# MCU.net
KiCad netlist of a schematic drawn in Altium Designer
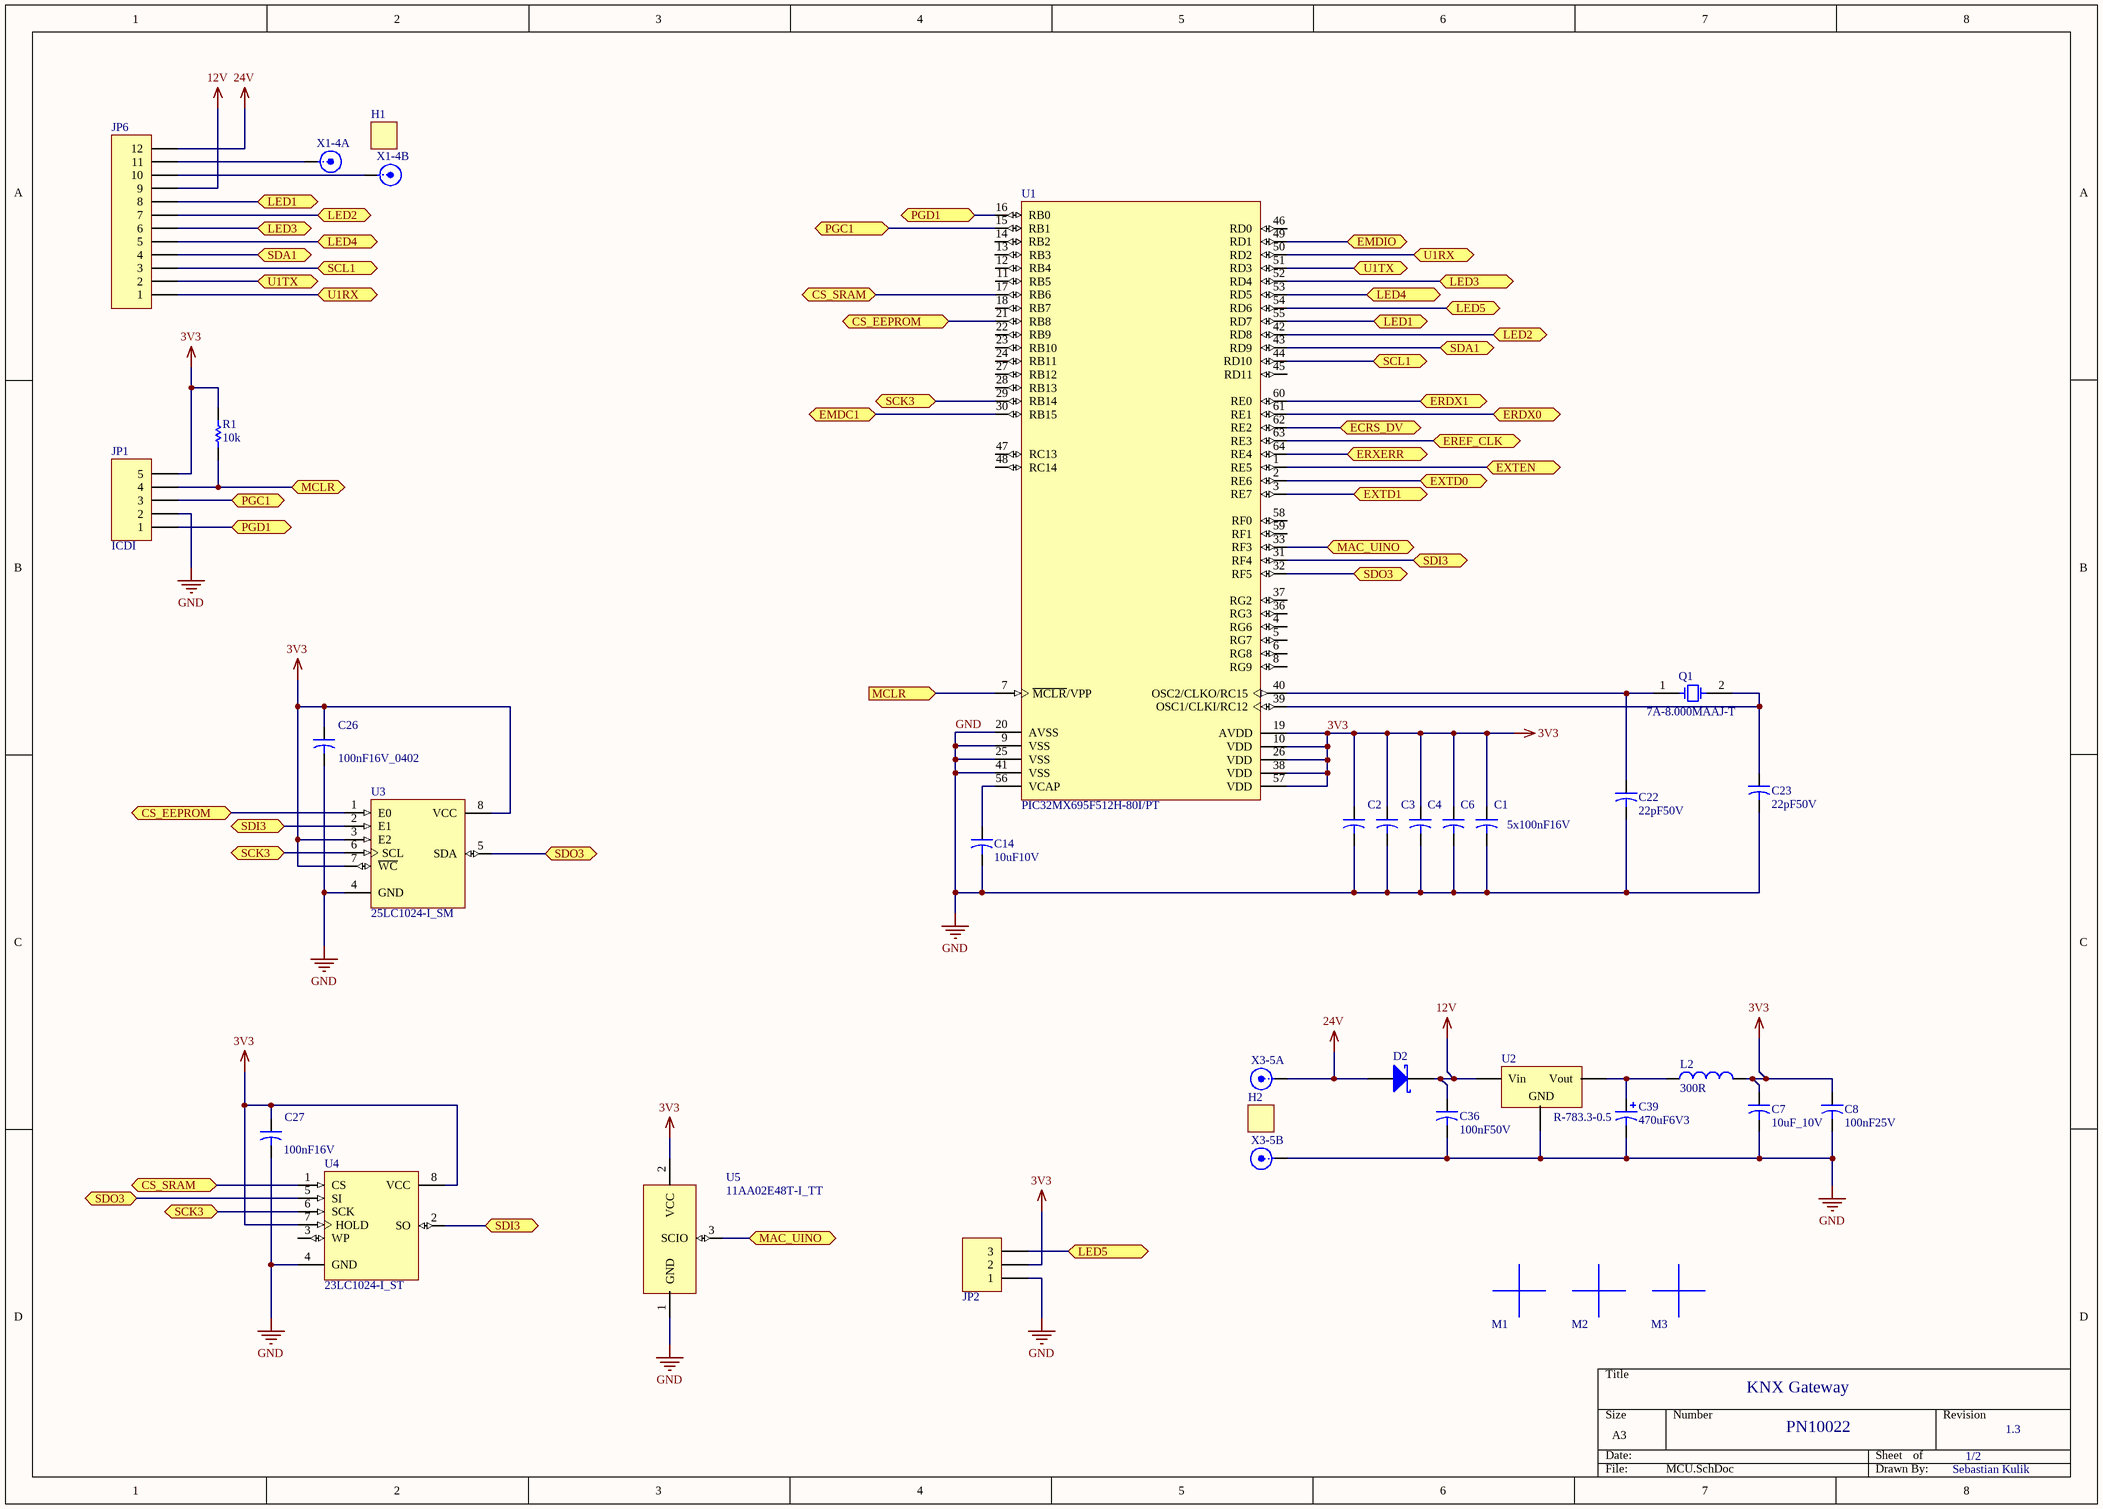
[diagram p0: MCU.SchDoc]

(export (version "E")
  (design (tool "Eeschema 10.0.6"))
  (components
    (comp (ref "C1")
      (value "100nF16V_0402")
      (footprint "C0402")
      (description "Capacitor")
      (fields (field (name "MANUFACTURER") "TDK") (field (name "PUBLISHER") "Sebastian Kulik"))
      (libsource (lib "Capacitors") (part "100nF16V_0402"))
    )
    (comp (ref "C2")
      (value "100nF16V_0402")
      (footprint "C0402")
      (description "Capacitor")
      (fields (field (name "MANUFACTURER") "TDK") (field (name "PUBLISHER") "Sebastian Kulik"))
      (libsource (lib "Capacitors") (part "100nF16V_0402"))
    )
    (comp (ref "C3")
      (value "100nF16V_0402")
      (footprint "C0402")
      (description "Capacitor")
      (fields (field (name "MANUFACTURER") "TDK") (field (name "PUBLISHER") "Sebastian Kulik"))
      (libsource (lib "Capacitors") (part "100nF16V_0402"))
    )
    (comp (ref "C4")
      (value "100nF16V_0402")
      (footprint "C0402")
      (description "Capacitor")
      (fields (field (name "MANUFACTURER") "TDK") (field (name "PUBLISHER") "Sebastian Kulik"))
      (libsource (lib "Capacitors") (part "100nF16V_0402"))
    )
    (comp (ref "C6")
      (value "100nF16V_0402")
      (footprint "C0402")
      (description "Capacitor")
      (fields (field (name "MANUFACTURER") "TDK") (field (name "PUBLISHER") "Sebastian Kulik"))
      (libsource (lib "Capacitors") (part "100nF16V_0402"))
    )
    (comp (ref "C7")
      (value "10uF_10V")
      (footprint "C0603")
      (description "AVX ,  X5R, 20%, 10V")
      (fields
        (field (name "MANUFACTURER") "AVX")
        (field (name "Comment") "10uF10V_0603")
        (field (name "PUBLISHER") "Sebastian Kulik")
      )
      (libsource (lib "Capacitors") (part "10uF10V_0603"))
    )
    (comp (ref "C8")
      (value "100nF25V")
      (footprint "C0402")
      (description "AVX, X5R, 10%, 25V")
      (fields
        (field (name "MANUFACTURER") "AVX")
        (field (name "Comment") "100nF25V_0402")
        (field (name "PUBLISHER") "Sebastian Kulik")
      )
      (libsource (lib "Capacitors") (part "100nF25V_0402"))
    )
    (comp (ref "C14")
      (value "10uF10V")
      (footprint "C0603")
      (description "Capacitor")
      (fields
        (field (name "MANUFACTURER") "AVX")
        (field (name "Comment") "10uF10V_0603")
        (field (name "PUBLISHER") "Sebastian Kulik")
      )
      (libsource (lib "Capacitors") (part "10uF10V_0603"))
    )
    (comp (ref "C22")
      (value "22pF50V")
      (footprint "C0402")
      (description "AVX, 50V")
      (fields
        (field (name "MANUFACTURER") "AVX")
        (field (name "Comment") "22pF50V_0402-AVX")
        (field (name "PUBLISHER") "Sebastian Kulik")
      )
      (libsource (lib "Capacitors") (part "22pF50V_0402-AVX"))
    )
    (comp (ref "C23")
      (value "22pF50V")
      (footprint "C0402")
      (description "AVX, 50V")
      (fields
        (field (name "MANUFACTURER") "AVX")
        (field (name "Comment") "22pF50V_0402-AVX")
        (field (name "PUBLISHER") "Sebastian Kulik")
      )
      (libsource (lib "Capacitors") (part "22pF50V_0402-AVX"))
    )
    (comp (ref "C26")
      (value "100nF16V_0402")
      (footprint "C0402")
      (description "Capacitor")
      (fields (field (name "MANUFACTURER") "TDK") (field (name "PUBLISHER") "Sebastian Kulik"))
      (libsource (lib "Capacitors") (part "100nF16V_0402"))
    )
    (comp (ref "C27")
      (value "100nF16V")
      (footprint "C0402")
      (description "Capacitor")
      (fields
        (field (name "MANUFACTURER") "TDK")
        (field (name "Comment") "100nF16V_0402")
        (field (name "PUBLISHER") "Sebastian Kulik")
      )
      (libsource (lib "Capacitors") (part "100nF16V_0402"))
    )
    (comp (ref "C36")
      (value "100nF50V")
      (footprint "C0402")
      (description "C series, X5R, 10%, 50V")
      (fields
        (field (name "MANUFACTURER") "TDK")
        (field (name "Comment") "100n50V_0402")
        (field (name "PUBLISHER") "Sebastian Kulik")
      )
      (libsource (lib "Capacitors") (part "100n50V_0402"))
    )
    (comp (ref "C39")
      (value "470uF6V3")
      (footprint "Panasonic_TPE-D4")
      (description "TPE-4D series, tantal, 10%, 6.3V")
      (fields
        (field (name "MANUFACTURER") "Panasonic")
        (field (name "Comment") "470uF_6V3_TPE-4D")
        (field (name "PUBLISHER") "Sebastian Kulik")
      )
      (libsource (lib "Capacitors") (part "470uF_6V3_TPE-4D"))
    )
    (comp (ref "D2")
      (value "RB160M-30TR")
      (footprint "SOD123")
      (description "Diode Schottky,2A,40V")
      (fields (field (name "MANUFACTURER") "Rohm") (field (name "PUBLISHER") "Sebastian Kulik"))
      (libsource (lib "Discrete") (part "RB160M-30TR"))
    )
    (comp (ref "H1")
      (value "Wago-243-211")
      (footprint "WAGO-243-211")
      (fields (field (name "MANUFACTURER") "Wago") (field (name "PUBLISHER") "Sebastian Kulik"))
      (libsource (lib "Connectors") (part "Wago-243-211"))
    )
    (comp (ref "H2")
      (value "Wago-243-211")
      (footprint "WAGO-243-211")
      (fields (field (name "MANUFACTURER") "Wago") (field (name "PUBLISHER") "Sebastian Kulik"))
      (libsource (lib "Connectors") (part "Wago-243-211"))
    )
    (comp (ref "JP1")
      (value "ICDI")
      (footprint "HDR1X5-1.27")
      (description "Header, 5-Pin")
      (fields (field (name "PUBLISHER") "Sebastian Kulik"))
      (libsource (lib "Connectors") (part "ICDI"))
    )
    (comp (ref "JP2")
      (value "Header-3")
      (footprint "HDR1X3")
      (description "Header-3-Pin")
      (fields (field (name "PUBLISHER") "Sebastian Kulik"))
      (libsource (lib "Connectors") (part "Header-3"))
    )
    (comp (ref "JP6")
      (value "Plug_12_2.54")
      (footprint "HDR1X12_2.54")
      (description "Plug, 11-Pin")
      (fields (field (name "MANUFACTURER") "WE") (field (name "PUBLISHER") "Sebastian Kulik"))
      (libsource (lib "Connectors") (part "Plug_12_2.54"))
    )
    (comp (ref "L2")
      (value "300R")
      (footprint "L0603")
      (description "WE, Ferrit, 300Rx2A")
      (fields
        (field (name "MANUFACTURER") "WE")
        (field (name "Comment") "300R2A_0603")
        (field (name "PUBLISHER") "Sebastian Kulik")
      )
      (libsource (lib "Passives") (part "300R2A_0603"))
    )
    (comp (ref "M1") (value "Paste-Mark") (footprint "Mark-3mm") (libsource (lib "Symbols") (part "Mark")))
    (comp (ref "M2") (value "Paste-Mark") (footprint "Mark-3mm") (libsource (lib "Symbols") (part "Mark")))
    (comp (ref "M3") (value "Paste-Mark") (footprint "Mark-3mm") (libsource (lib "Symbols") (part "Mark")))
    (comp (ref "Q1")
      (value "7A-8.000MAAJ-T")
      (footprint "TXC_7A")
      (description "Crystal, 7A-8.000MAAJ-T")
      (fields (field (name "MANUFACTURER") "TXC") (field (name "PUBLISHER") "Sebastian Kulik"))
      (libsource (lib "Passives") (part "Crystal_8MHz"))
    )
    (comp (ref "R1")
      (value "10k")
      (footprint "R0402")
      (description "Vishay CRCW series, 125mW, 1%")
      (fields
        (field (name "MANUFACTURER") "Vishay")
        (field (name "Comment") "10k_0402")
        (field (name "PUBLISHER") "Sebastian Kulik")
      )
      (libsource (lib "Resistors") (part "10k_0402"))
    )
    (comp (ref "U1")
      (value "PIC32MX695F512H-80I/PT")
      (footprint "TQFP-64_N1")
      (fields (field (name "MANUFACTURER") "Microchip") (field (name "PUBLISHER") "Sebastian Kulik"))
      (libsource (lib "ICs") (part "PIC32MX695F512H-80I/PT"))
    )
    (comp (ref "U2")
      (value "R-783.3-0.5")
      (footprint "R-783_3-0_5")
      (description "Voltage Regulator")
      (fields (field (name "MANUFACTURER") "Recom") (field (name "PUBLISHER") "Sebastian Kulik"))
      (libsource (lib "ICs") (part "Recom-R-783_3-0_5"))
    )
    (comp (ref "U3")
      (value "25LC1024-I_SM")
      (footprint "SOP8_N")
      (description "1024 Kbit Serial SPI Bus EEPROM")
      (fields (field (name "MANUFACTURER") "Microchip") (field (name "PUBLISHER") "Sebastian Kulik"))
      (libsource (lib "ICs") (part "25LC1024-I_SM"))
    )
    (comp (ref "U4")
      (value "23LC1024-I_ST")
      (footprint "TSSOP8")
      (description "1 Mbit Serial  EEPROM")
      (fields (field (name "MANUFACTURER") "Microchip") (field (name "PUBLISHER") "Sebastian Kulik"))
      (libsource (lib "ICs") (part "23LC1024-I_ST"))
    )
    (comp (ref "U5")
      (value "11AA02E48T-I_TT")
      (footprint "SOT23_M")
      (description "2 kbit Serial  EEPROM")
      (fields (field (name "MANUFACTURER") "Microchip") (field (name "PUBLISHER") "Sebastian Kulik"))
      (libsource (lib "ICs") (part "11AA02E48T-I_TT"))
    )
    (comp (ref "X1-4")
      (value "Wago-243-131")
      (footprint "WAGO-243-131")
      (fields (field (name "MANUFACTURER") "Wago") (field (name "PUBLISHER") "Sebastian Kulik"))
      (libsource (lib "") (part "Wago-243-131_2"))
    )
    (comp (ref "X3-5")
      (value "Wago-243-131")
      (footprint "WAGO-243-131")
      (fields (field (name "MANUFACTURER") "Wago") (field (name "PUBLISHER") "Sebastian Kulik"))
      (libsource (lib "") (part "Wago-243-131_1"))
    )
  )
  (nets
    (net (code "1") (name "/CS_EEPROM") (class "Default")
      (node (ref "U1") (pin "21") (pinfunction "RB8_21") (pintype "bidirectional"))
      (node (ref "U3") (pin "1") (pinfunction "E0_1") (pintype "input"))
    )
    (net (code "2") (name "/CS_SRAM") (class "Default")
      (node (ref "U1") (pin "17") (pinfunction "RB6_17") (pintype "bidirectional"))
      (node (ref "U4") (pin "1") (pinfunction "CS_1") (pintype "input"))
    )
    (net (code "3") (name "/ECRS_DV") (class "Default")
      (node (ref "U1") (pin "62") (pinfunction "RE2_62") (pintype "bidirectional"))
    )
    (net (code "4") (name "/EMDC1") (class "Default")
      (node (ref "U1") (pin "30") (pinfunction "RB15_30") (pintype "bidirectional"))
    )
    (net (code "5") (name "/EMDIO") (class "Default")
      (node (ref "U1") (pin "49") (pinfunction "RD1_49") (pintype "bidirectional"))
    )
    (net (code "6") (name "/ERDX0") (class "Default")
      (node (ref "U1") (pin "61") (pinfunction "RE1_61") (pintype "bidirectional"))
    )
    (net (code "7") (name "/ERDX1") (class "Default")
      (node (ref "U1") (pin "60") (pinfunction "RE0_60") (pintype "bidirectional"))
    )
    (net (code "8") (name "/EREF_CLK") (class "Default")
      (node (ref "U1") (pin "63") (pinfunction "RE3_63") (pintype "bidirectional"))
    )
    (net (code "9") (name "/ERXERR") (class "Default")
      (node (ref "U1") (pin "64") (pinfunction "RE4_64") (pintype "bidirectional"))
    )
    (net (code "10") (name "/EXTD0") (class "Default")
      (node (ref "U1") (pin "2") (pinfunction "RE6_2") (pintype "bidirectional"))
    )
    (net (code "11") (name "/EXTD1") (class "Default")
      (node (ref "U1") (pin "3") (pinfunction "RE7_3") (pintype "bidirectional"))
    )
    (net (code "12") (name "/EXTEN") (class "Default")
      (node (ref "U1") (pin "1") (pinfunction "RE5_1") (pintype "bidirectional"))
    )
    (net (code "13") (name "/LED1") (class "Default")
      (node (ref "JP6") (pin "8") (pinfunction "8_8") (pintype "passive"))
      (node (ref "U1") (pin "55") (pinfunction "RD7_55") (pintype "bidirectional"))
    )
    (net (code "14") (name "/LED2") (class "Default")
      (node (ref "JP6") (pin "7") (pinfunction "7_7") (pintype "passive"))
      (node (ref "U1") (pin "42") (pinfunction "RD8_42") (pintype "bidirectional"))
    )
    (net (code "15") (name "/LED3") (class "Default")
      (node (ref "JP6") (pin "6") (pinfunction "6_6") (pintype "passive"))
      (node (ref "U1") (pin "52") (pinfunction "RD4_52") (pintype "bidirectional"))
    )
    (net (code "16") (name "/LED4") (class "Default")
      (node (ref "JP6") (pin "5") (pinfunction "5_5") (pintype "passive"))
      (node (ref "U1") (pin "53") (pinfunction "RD5_53") (pintype "bidirectional"))
    )
    (net (code "17") (name "/LED5") (class "Default")
      (node (ref "JP2") (pin "3") (pinfunction "3_3") (pintype "passive"))
      (node (ref "U1") (pin "54") (pinfunction "RD6_54") (pintype "bidirectional"))
    )
    (net (code "18") (name "/MAC_UINO") (class "Default")
      (node (ref "U1") (pin "33") (pinfunction "RF3_33") (pintype "bidirectional"))
      (node (ref "U5") (pin "3") (pinfunction "SCIO_3") (pintype "bidirectional"))
    )
    (net (code "19") (name "/MCLR") (class "Default")
      (node (ref "JP1") (pin "4") (pinfunction "4_4") (pintype "passive"))
      (node (ref "R1") (pin "1") (pinfunction "1_1") (pintype "passive"))
      (node (ref "U1") (pin "7") (pinfunction "~{MCLR}/VPP_7") (pintype "input"))
    )
    (net (code "20") (name "/PGC1") (class "Default")
      (node (ref "JP1") (pin "3") (pinfunction "3_3") (pintype "passive"))
      (node (ref "U1") (pin "15") (pinfunction "RB1_15") (pintype "bidirectional"))
    )
    (net (code "21") (name "/PGD1") (class "Default")
      (node (ref "JP1") (pin "1") (pinfunction "1_1") (pintype "passive"))
      (node (ref "U1") (pin "16") (pinfunction "RB0_16") (pintype "bidirectional"))
    )
    (net (code "22") (name "/SCK3") (class "Default")
      (node (ref "U1") (pin "29") (pinfunction "RB14_29") (pintype "bidirectional"))
      (node (ref "U3") (pin "6") (pinfunction "SCL_6") (pintype "input"))
      (node (ref "U4") (pin "6") (pinfunction "SCK_6") (pintype "input"))
    )
    (net (code "23") (name "/SCL1") (class "Default")
      (node (ref "JP6") (pin "3") (pinfunction "3_3") (pintype "passive"))
      (node (ref "U1") (pin "44") (pinfunction "RD10_44") (pintype "bidirectional"))
    )
    (net (code "24") (name "/SDA1") (class "Default")
      (node (ref "JP6") (pin "4") (pinfunction "4_4") (pintype "passive"))
      (node (ref "U1") (pin "43") (pinfunction "RD9_43") (pintype "bidirectional"))
    )
    (net (code "25") (name "/SDI3") (class "Default")
      (node (ref "U1") (pin "31") (pinfunction "RF4_31") (pintype "bidirectional"))
      (node (ref "U3") (pin "2") (pinfunction "E1_2") (pintype "input"))
      (node (ref "U4") (pin "2") (pinfunction "SO_2") (pintype "bidirectional"))
    )
    (net (code "26") (name "/SDO3") (class "Default")
      (node (ref "U1") (pin "32") (pinfunction "RF5_32") (pintype "bidirectional"))
      (node (ref "U3") (pin "5") (pinfunction "SDA_5") (pintype "bidirectional"))
      (node (ref "U4") (pin "5") (pinfunction "SI_5") (pintype "input"))
    )
    (net (code "27") (name "/U1RX") (class "Default")
      (node (ref "JP6") (pin "1") (pinfunction "1_1") (pintype "passive"))
      (node (ref "U1") (pin "50") (pinfunction "RD2_50") (pintype "bidirectional"))
    )
    (net (code "28") (name "/U1TX") (class "Default")
      (node (ref "JP6") (pin "2") (pinfunction "2_2") (pintype "passive"))
      (node (ref "U1") (pin "51") (pinfunction "RD3_51") (pintype "bidirectional"))
    )
    (net (code "29") (name "3V3") (class "Default")
      (node (ref "C1") (pin "1") (pinfunction "1_1") (pintype "passive"))
      (node (ref "C2") (pin "1") (pinfunction "1_1") (pintype "passive"))
      (node (ref "C26") (pin "1") (pinfunction "1_1") (pintype "passive"))
      (node (ref "C27") (pin "1") (pinfunction "1_1") (pintype "passive"))
      (node (ref "C3") (pin "1") (pinfunction "1_1") (pintype "passive"))
      (node (ref "C4") (pin "1") (pinfunction "1_1") (pintype "passive"))
      (node (ref "C6") (pin "1") (pinfunction "1_1") (pintype "passive"))
      (node (ref "C7") (pin "1") (pinfunction "1_1") (pintype "passive"))
      (node (ref "C8") (pin "1") (pinfunction "1_1") (pintype "passive"))
      (node (ref "JP1") (pin "5") (pinfunction "5_5") (pintype "passive"))
      (node (ref "JP2") (pin "2") (pinfunction "2_2") (pintype "passive"))
      (node (ref "L2") (pin "2") (pinfunction "2_2") (pintype "passive"))
      (node (ref "R1") (pin "2") (pinfunction "2_2") (pintype "passive"))
      (node (ref "U1") (pin "10") (pinfunction "VDD_10") (pintype "power_in"))
      (node (ref "U1") (pin "19") (pinfunction "AVDD_19") (pintype "power_in"))
      (node (ref "U1") (pin "26") (pinfunction "VDD_26") (pintype "power_in"))
      (node (ref "U1") (pin "38") (pinfunction "VDD_38") (pintype "power_in"))
      (node (ref "U1") (pin "57") (pinfunction "VDD_57") (pintype "power_in"))
      (node (ref "U3") (pin "3") (pinfunction "E2_3") (pintype "input"))
      (node (ref "U3") (pin "7") (pinfunction "~{WC}_7") (pintype "bidirectional"))
      (node (ref "U3") (pin "8") (pinfunction "VCC_8") (pintype "power_in"))
      (node (ref "U4") (pin "7") (pinfunction "HOLD_7") (pintype "input"))
      (node (ref "U4") (pin "8") (pinfunction "VCC_8") (pintype "power_in"))
      (node (ref "U5") (pin "2") (pinfunction "VCC_2") (pintype "power_in"))
    )
    (net (code "30") (name "12V") (class "Default")
      (node (ref "C36") (pin "1") (pinfunction "1_1") (pintype "passive"))
      (node (ref "D2") (pin "1") (pinfunction "K_1") (pintype "passive"))
      (node (ref "JP6") (pin "9") (pinfunction "9_9") (pintype "passive"))
      (node (ref "U2") (pin "1") (pinfunction "Vin_1") (pintype "passive"))
    )
    (net (code "31") (name "24V") (class "Default")
      (node (ref "D2") (pin "2") (pinfunction "A_2") (pintype "passive"))
      (node (ref "JP6") (pin "12") (pinfunction "12_12") (pintype "passive"))
      (node (ref "X3-5") (pin "1") (pinfunction "X_1") (pintype "passive"))
    )
    (net (code "32") (name "GND") (class "Default")
      (node (ref "C1") (pin "2") (pinfunction "2_2") (pintype "passive"))
      (node (ref "C14") (pin "2") (pinfunction "2_2") (pintype "passive"))
      (node (ref "C2") (pin "2") (pinfunction "2_2") (pintype "passive"))
      (node (ref "C22") (pin "2") (pinfunction "2_2") (pintype "passive"))
      (node (ref "C23") (pin "2") (pinfunction "2_2") (pintype "passive"))
      (node (ref "C26") (pin "2") (pinfunction "2_2") (pintype "passive"))
      (node (ref "C27") (pin "2") (pinfunction "2_2") (pintype "passive"))
      (node (ref "C3") (pin "2") (pinfunction "2_2") (pintype "passive"))
      (node (ref "C36") (pin "2") (pinfunction "2_2") (pintype "passive"))
      (node (ref "C39") (pin "2") (pinfunction "2_2") (pintype "passive"))
      (node (ref "C4") (pin "2") (pinfunction "2_2") (pintype "passive"))
      (node (ref "C6") (pin "2") (pinfunction "2_2") (pintype "passive"))
      (node (ref "C7") (pin "2") (pinfunction "2_2") (pintype "passive"))
      (node (ref "C8") (pin "2") (pinfunction "2_2") (pintype "passive"))
      (node (ref "JP1") (pin "2") (pinfunction "2_2") (pintype "passive"))
      (node (ref "JP2") (pin "1") (pinfunction "1_1") (pintype "passive"))
      (node (ref "U1") (pin "20") (pinfunction "AVSS_20") (pintype "power_in"))
      (node (ref "U1") (pin "25") (pinfunction "VSS_25") (pintype "power_in"))
      (node (ref "U1") (pin "41") (pinfunction "VSS_41") (pintype "power_in"))
      (node (ref "U1") (pin "9") (pinfunction "VSS_9") (pintype "power_in"))
      (node (ref "U2") (pin "2") (pinfunction "GND_2") (pintype "passive"))
      (node (ref "U3") (pin "4") (pinfunction "GND_4") (pintype "power_in"))
      (node (ref "U4") (pin "4") (pinfunction "GND_4") (pintype "power_in"))
      (node (ref "U5") (pin "1") (pinfunction "GND_1") (pintype "power_in"))
      (node (ref "X3-5") (pin "2") (pinfunction "Y_2") (pintype "passive"))
    )
    (net (code "33") (name "Net-(Q1-E{slash}D)") (class "Default")
      (node (ref "C22") (pin "1") (pinfunction "1_1") (pintype "passive"))
      (node (ref "Q1") (pin "1") (pinfunction "E/D_1") (pintype "passive"))
      (node (ref "U1") (pin "40") (pinfunction "OSC2/CLKO/RC15_40") (pintype "output"))
    )
    (net (code "34") (name "Net-(Q1-GND)") (class "Default")
      (node (ref "C23") (pin "1") (pinfunction "1_1") (pintype "passive"))
      (node (ref "Q1") (pin "2") (pinfunction "GND_2") (pintype "passive"))
      (node (ref "U1") (pin "39") (pinfunction "OSC1/CLKI/RC12_39") (pintype "bidirectional"))
    )
    (net (code "35") (name "Net-(U1-VCAP)") (class "Default")
      (node (ref "C14") (pin "1") (pinfunction "1_1") (pintype "passive"))
      (node (ref "U1") (pin "56") (pinfunction "VCAP_56") (pintype "power_in"))
    )
    (net (code "36") (name "Net-(U2-Vout)") (class "Default")
      (node (ref "C39") (pin "1") (pinfunction "1_1") (pintype "passive"))
      (node (ref "L2") (pin "1") (pinfunction "1_1") (pintype "passive"))
      (node (ref "U2") (pin "3") (pinfunction "Vout_3") (pintype "passive"))
    )
    (net (code "37") (name "Net-(X1-4A-X)") (class "Default")
      (node (ref "JP6") (pin "11") (pinfunction "11_11") (pintype "passive"))
      (node (ref "X1-4") (pin "1") (pinfunction "X_1") (pintype "passive"))
    )
    (net (code "38") (name "Net-(X1-4B-Y)") (class "Default")
      (node (ref "JP6") (pin "10") (pinfunction "10_10") (pintype "passive"))
      (node (ref "X1-4") (pin "2") (pinfunction "Y_2") (pintype "passive"))
    )
    (net (code "39") (name "unconnected-(U1-RB2-Pad14)") (class "Default")
      (node (ref "U1") (pin "14") (pinfunction "RB2_14") (pintype "bidirectional"))
    )
    (net (code "40") (name "unconnected-(U1-RB3-Pad13)") (class "Default")
      (node (ref "U1") (pin "13") (pinfunction "RB3_13") (pintype "bidirectional"))
    )
    (net (code "41") (name "unconnected-(U1-RB4-Pad12)") (class "Default")
      (node (ref "U1") (pin "12") (pinfunction "RB4_12") (pintype "bidirectional"))
    )
    (net (code "42") (name "unconnected-(U1-RB5-Pad11)") (class "Default")
      (node (ref "U1") (pin "11") (pinfunction "RB5_11") (pintype "bidirectional"))
    )
    (net (code "43") (name "unconnected-(U1-RB7-Pad18)") (class "Default")
      (node (ref "U1") (pin "18") (pinfunction "RB7_18") (pintype "bidirectional"))
    )
    (net (code "44") (name "unconnected-(U1-RB9-Pad22)") (class "Default")
      (node (ref "U1") (pin "22") (pinfunction "RB9_22") (pintype "bidirectional"))
    )
    (net (code "45") (name "unconnected-(U1-RB10-Pad23)") (class "Default")
      (node (ref "U1") (pin "23") (pinfunction "RB10_23") (pintype "bidirectional"))
    )
    (net (code "46") (name "unconnected-(U1-RB11-Pad24)") (class "Default")
      (node (ref "U1") (pin "24") (pinfunction "RB11_24") (pintype "bidirectional"))
    )
    (net (code "47") (name "unconnected-(U1-RB12-Pad27)") (class "Default")
      (node (ref "U1") (pin "27") (pinfunction "RB12_27") (pintype "bidirectional"))
    )
    (net (code "48") (name "unconnected-(U1-RB13-Pad28)") (class "Default")
      (node (ref "U1") (pin "28") (pinfunction "RB13_28") (pintype "bidirectional"))
    )
    (net (code "49") (name "unconnected-(U1-RC13-Pad47)") (class "Default")
      (node (ref "U1") (pin "47") (pinfunction "RC13_47") (pintype "bidirectional"))
    )
    (net (code "50") (name "unconnected-(U1-RC14-Pad48)") (class "Default")
      (node (ref "U1") (pin "48") (pinfunction "RC14_48") (pintype "bidirectional"))
    )
    (net (code "51") (name "unconnected-(U1-RD0-Pad46)") (class "Default")
      (node (ref "U1") (pin "46") (pinfunction "RD0_46") (pintype "bidirectional"))
    )
    (net (code "52") (name "unconnected-(U1-RD11-Pad45)") (class "Default")
      (node (ref "U1") (pin "45") (pinfunction "RD11_45") (pintype "bidirectional"))
    )
    (net (code "53") (name "unconnected-(U1-RF0-Pad58)") (class "Default")
      (node (ref "U1") (pin "58") (pinfunction "RF0_58") (pintype "bidirectional"))
    )
    (net (code "54") (name "unconnected-(U1-RF1-Pad59)") (class "Default")
      (node (ref "U1") (pin "59") (pinfunction "RF1_59") (pintype "bidirectional"))
    )
    (net (code "55") (name "unconnected-(U1-RG2-Pad37)") (class "Default")
      (node (ref "U1") (pin "37") (pinfunction "RG2_37") (pintype "bidirectional"))
    )
    (net (code "56") (name "unconnected-(U1-RG3-Pad36)") (class "Default")
      (node (ref "U1") (pin "36") (pinfunction "RG3_36") (pintype "bidirectional"))
    )
    (net (code "57") (name "unconnected-(U1-RG6-Pad4)") (class "Default")
      (node (ref "U1") (pin "4") (pinfunction "RG6_4") (pintype "bidirectional"))
    )
    (net (code "58") (name "unconnected-(U1-RG7-Pad5)") (class "Default")
      (node (ref "U1") (pin "5") (pinfunction "RG7_5") (pintype "bidirectional"))
    )
    (net (code "59") (name "unconnected-(U1-RG8-Pad6)") (class "Default")
      (node (ref "U1") (pin "6") (pinfunction "RG8_6") (pintype "bidirectional"))
    )
    (net (code "60") (name "unconnected-(U1-RG9-Pad8)") (class "Default")
      (node (ref "U1") (pin "8") (pinfunction "RG9_8") (pintype "bidirectional"))
    )
    (net (code "61") (name "unconnected-(U4-WP-Pad3)") (class "Default")
      (node (ref "U4") (pin "3") (pinfunction "WP_3") (pintype "bidirectional"))
    )
  )
)
